# ADC_CURRENT_PUMP.net
KiCad netlist of a schematic drawn in Altium Designer
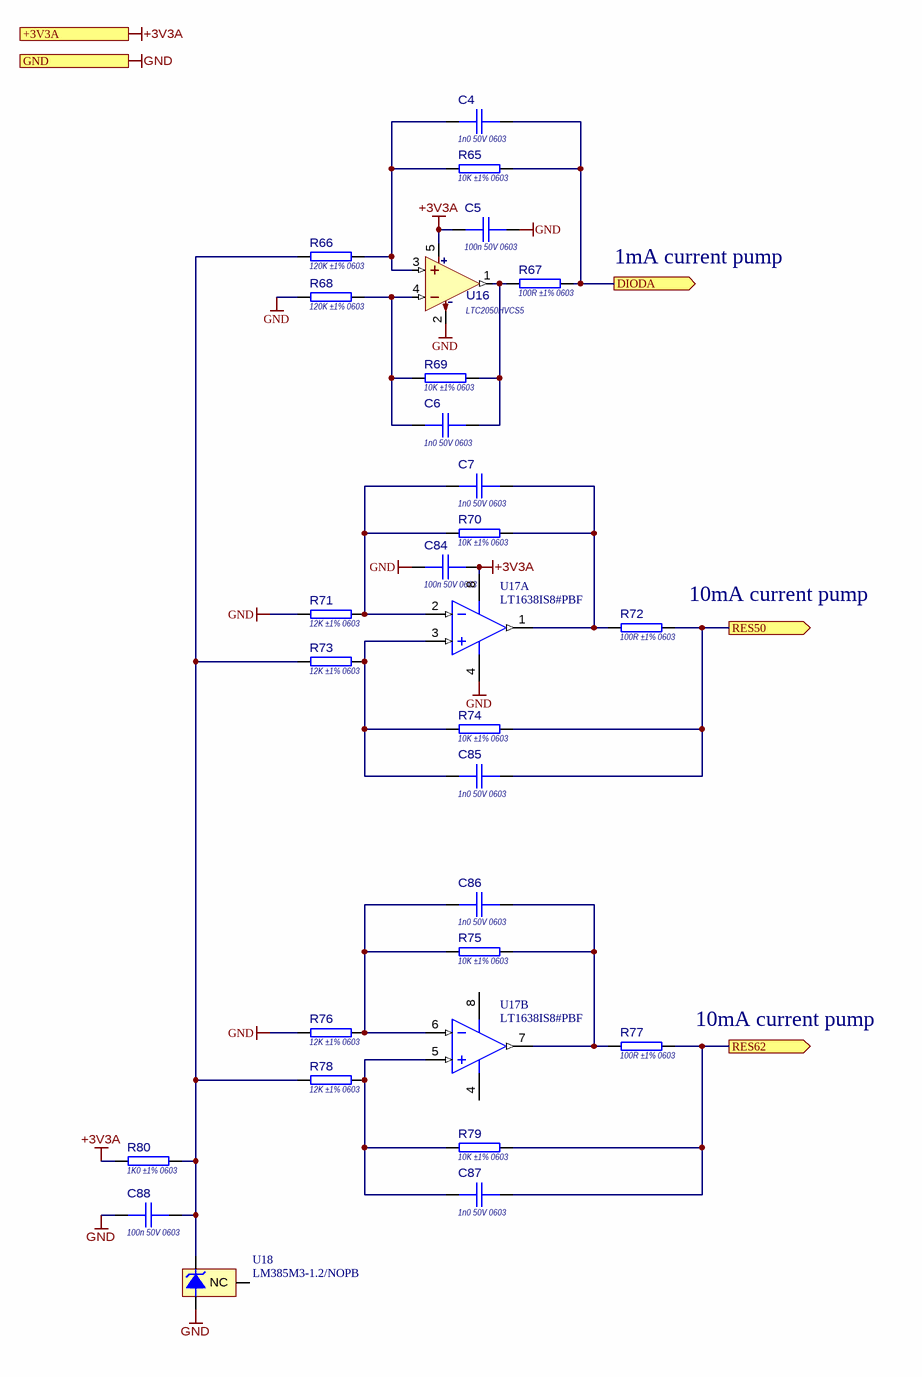
[diagram p0: ADC_CURRENT_PUMP.SchDoc]

(export (version "E")
  (design (tool "Eeschema 10.0.6"))
  (components
    (comp (ref "C4")
      (value "1n0 50V 0603")
      (footprint "CAPC1608X90N")
      (description "1n0 50V X7R ±10% 0603 (1608 metric)")
      (fields (field (name "PARTNUMBER") "GRM188R71H102KA01") (field (name "TOLERANCE") "±10%"))
      (libsource (lib "Omnisys Vault") (part "CAP-2PIN"))
    )
    (comp (ref "C5")
      (value "100n 50V 0603")
      (footprint "CAPC1608X90N")
      (description "100n 50V X7R ±10% 0603 (1608 metric)")
      (fields (field (name "PARTNUMBER") "GRM188R71H104KA93") (field (name "TOLERANCE") "±10%"))
      (libsource (lib "Omnisys Vault") (part "CAP-2PIN"))
    )
    (comp (ref "C6")
      (value "1n0 50V 0603")
      (footprint "CAPC1608X90N")
      (description "1n0 50V X7R ±10% 0603 (1608 metric)")
      (fields (field (name "PARTNUMBER") "GRM188R71H102KA01") (field (name "TOLERANCE") "±10%"))
      (libsource (lib "Omnisys Vault") (part "CAP-2PIN"))
    )
    (comp (ref "C7")
      (value "1n0 50V 0603")
      (footprint "CAPC1608X90N")
      (description "1n0 50V X7R ±10% 0603 (1608 metric)")
      (fields (field (name "PARTNUMBER") "GRM188R71H102KA01") (field (name "TOLERANCE") "±10%"))
      (libsource (lib "Omnisys Vault") (part "CAP-2PIN"))
    )
    (comp (ref "C84")
      (value "100n 50V 0603")
      (footprint "CAPC1608X90N")
      (description "100n 50V X7R ±10% 0603 (1608 metric)")
      (fields (field (name "PARTNUMBER") "GRM188R71H104KA93") (field (name "TOLERANCE") "±10%"))
      (libsource (lib "Omnisys Vault") (part "CAP-2PIN"))
    )
    (comp (ref "C85")
      (value "1n0 50V 0603")
      (footprint "CAPC1608X90N")
      (description "1n0 50V X7R ±10% 0603 (1608 metric)")
      (fields (field (name "PARTNUMBER") "GRM188R71H102KA01") (field (name "TOLERANCE") "±10%"))
      (libsource (lib "Omnisys Vault") (part "CAP-2PIN"))
    )
    (comp (ref "C86")
      (value "1n0 50V 0603")
      (footprint "CAPC1608X90N")
      (description "1n0 50V X7R ±10% 0603 (1608 metric)")
      (fields (field (name "PARTNUMBER") "GRM188R71H102KA01") (field (name "TOLERANCE") "±10%"))
      (libsource (lib "Omnisys Vault") (part "CAP-2PIN"))
    )
    (comp (ref "C87")
      (value "1n0 50V 0603")
      (footprint "CAPC1608X90N")
      (description "1n0 50V X7R ±10% 0603 (1608 metric)")
      (fields (field (name "PARTNUMBER") "GRM188R71H102KA01") (field (name "TOLERANCE") "±10%"))
      (libsource (lib "Omnisys Vault") (part "CAP-2PIN"))
    )
    (comp (ref "C88")
      (value "100n 50V 0603")
      (footprint "CAPC1608X90N")
      (description "100n 50V X7R ±10% 0603 (1608 metric)")
      (fields (field (name "PARTNUMBER") "GRM188R71H104KA93") (field (name "TOLERANCE") "±10%"))
      (libsource (lib "Omnisys Vault") (part "CAP-2PIN"))
    )
    (comp (ref "R65")
      (value "10K ±1% 0603")
      (footprint "RESC1608N")
      (description "10K ±1% ±100 ppm/˚C 0.10W 75V 0603 (1608 metric)")
      (fields (field (name "POWER") "100mW") (field (name "TOLERANCE") "1%"))
      (libsource (lib "Omnisys Vault") (part "RES-2PIN"))
    )
    (comp (ref "R66")
      (value "120K ±1% 0603")
      (footprint "RESC1608N")
      (description "120K ±1% ±100 ppm/˚C 0.10W 75V 0603 (1608 metric)")
      (fields (field (name "POWER") "100mW") (field (name "TOLERANCE") "1%"))
      (libsource (lib "Omnisys Vault") (part "RES-2PIN"))
    )
    (comp (ref "R67")
      (value "100R ±1% 0603")
      (footprint "RESC1608N")
      (description "100R ±1% ±100 ppm/˚C 0.10W 75V 0603 (1608 metric)")
      (fields (field (name "POWER") "100mW") (field (name "TOLERANCE") "1%"))
      (libsource (lib "Omnisys Vault") (part "RES-2PIN"))
    )
    (comp (ref "R68")
      (value "120K ±1% 0603")
      (footprint "RESC1608N")
      (description "120K ±1% ±100 ppm/˚C 0.10W 75V 0603 (1608 metric)")
      (fields (field (name "POWER") "100mW") (field (name "TOLERANCE") "1%"))
      (libsource (lib "Omnisys Vault") (part "RES-2PIN"))
    )
    (comp (ref "R69")
      (value "10K ±1% 0603")
      (footprint "RESC1608N")
      (description "10K ±1% ±100 ppm/˚C 0.10W 75V 0603 (1608 metric)")
      (fields (field (name "POWER") "100mW") (field (name "TOLERANCE") "1%"))
      (libsource (lib "Omnisys Vault") (part "RES-2PIN"))
    )
    (comp (ref "R70")
      (value "10K ±1% 0603")
      (footprint "RESC1608N")
      (description "10K ±1% ±100 ppm/˚C 0.10W 75V 0603 (1608 metric)")
      (fields (field (name "POWER") "100mW") (field (name "TOLERANCE") "1%"))
      (libsource (lib "Omnisys Vault") (part "RES-2PIN"))
    )
    (comp (ref "R71")
      (value "12K ±1% 0603")
      (footprint "RESC1608N")
      (description "12K ±1% ±100 ppm/˚C 0.10W 75V 0603 (1608 metric)")
      (fields (field (name "POWER") "100mW") (field (name "TOLERANCE") "1%"))
      (libsource (lib "Omnisys Vault") (part "RES-2PIN"))
    )
    (comp (ref "R72")
      (value "100R ±1% 0603")
      (footprint "RESC1608N")
      (description "100R ±1% ±100 ppm/˚C 0.10W 75V 0603 (1608 metric)")
      (fields (field (name "POWER") "100mW") (field (name "TOLERANCE") "1%"))
      (libsource (lib "Omnisys Vault") (part "RES-2PIN"))
    )
    (comp (ref "R73")
      (value "12K ±1% 0603")
      (footprint "RESC1608N")
      (description "12K ±1% ±100 ppm/˚C 0.10W 75V 0603 (1608 metric)")
      (fields (field (name "POWER") "100mW") (field (name "TOLERANCE") "1%"))
      (libsource (lib "Omnisys Vault") (part "RES-2PIN"))
    )
    (comp (ref "R74")
      (value "10K ±1% 0603")
      (footprint "RESC1608N")
      (description "10K ±1% ±100 ppm/˚C 0.10W 75V 0603 (1608 metric)")
      (fields (field (name "POWER") "100mW") (field (name "TOLERANCE") "1%"))
      (libsource (lib "Omnisys Vault") (part "RES-2PIN"))
    )
    (comp (ref "R75")
      (value "10K ±1% 0603")
      (footprint "RESC1608N")
      (description "10K ±1% ±100 ppm/˚C 0.10W 75V 0603 (1608 metric)")
      (fields (field (name "POWER") "100mW") (field (name "TOLERANCE") "1%"))
      (libsource (lib "Omnisys Vault") (part "RES-2PIN"))
    )
    (comp (ref "R76")
      (value "12K ±1% 0603")
      (footprint "RESC1608N")
      (description "12K ±1% ±100 ppm/˚C 0.10W 75V 0603 (1608 metric)")
      (fields (field (name "POWER") "100mW") (field (name "TOLERANCE") "1%"))
      (libsource (lib "Omnisys Vault") (part "RES-2PIN"))
    )
    (comp (ref "R77")
      (value "100R ±1% 0603")
      (footprint "RESC1608N")
      (description "100R ±1% ±100 ppm/˚C 0.10W 75V 0603 (1608 metric)")
      (fields (field (name "POWER") "100mW") (field (name "TOLERANCE") "1%"))
      (libsource (lib "Omnisys Vault") (part "RES-2PIN"))
    )
    (comp (ref "R78")
      (value "12K ±1% 0603")
      (footprint "RESC1608N")
      (description "12K ±1% ±100 ppm/˚C 0.10W 75V 0603 (1608 metric)")
      (fields (field (name "POWER") "100mW") (field (name "TOLERANCE") "1%"))
      (libsource (lib "Omnisys Vault") (part "RES-2PIN"))
    )
    (comp (ref "R79")
      (value "10K ±1% 0603")
      (footprint "RESC1608N")
      (description "10K ±1% ±100 ppm/˚C 0.10W 75V 0603 (1608 metric)")
      (fields (field (name "POWER") "100mW") (field (name "TOLERANCE") "1%"))
      (libsource (lib "Omnisys Vault") (part "RES-2PIN"))
    )
    (comp (ref "R80")
      (value "1K0 ±1% 0603")
      (footprint "RESC1608N")
      (description "1K0 ±1% ±100 ppm/˚C 0.10W 75V 0603 (1608 metric)")
      (fields (field (name "TOLERANCE") "1%") (field (name "POWER") "100mW"))
      (libsource (lib "Omnisys Vault") (part "RES-2PIN"))
    )
    (comp (ref "U16")
      (value "LTC2050HVCS5")
      (footprint "SOT95P280X100-5N")
      (description "Zero-Drift Operational Amplifiers in SOT-23")
      (libsource (lib "Omnisys Vault") (part "OPAMP-SOT23-5"))
    )
    (comp (ref "U17")
      (value "LT1638IS8#PBF")
      (footprint "LT-S8-8_N")
      (fields
        (field (name "LINEAR TECHNOLOGY PART NUMBER") "LT1638")
        (field (name "MANUFACTURER") "Linear Technology")
      )
      (libsource (lib "Altium Content Vault") (part "LT-LT1638-S8-8"))
    )
    (comp (ref "U18")
      (value "LM385M3-1.2/NOPB")
      (footprint "DBZ0003A_L")
      (description "Micropower Voltage Reference Diode, 3-pin SOT-23, Pb-Free")
      (fields (field (name "MANUFACTURER") "Texas Instruments"))
      (libsource (lib "Altium Content Vault") (part "PM-REF-LM113-SOT3"))
    )
  )
  (nets
    (net (code "1") (name "+3V3A") (class "Default")
      (node (ref "C5") (pin "2") (pinfunction "2_2") (pintype "passive"))
      (node (ref "C84") (pin "2") (pinfunction "2_2") (pintype "passive"))
      (node (ref "R80") (pin "2") (pinfunction "2_2") (pintype "passive"))
      (node (ref "U16") (pin "5") (pinfunction "+V_5") (pintype "power_in"))
      (node (ref "U17") (pin "8") (pinfunction "V+_8") (pintype "power_in"))
    )
    (net (code "2") (name "/DIODA") (class "Default")
      (node (ref "C4") (pin "1") (pinfunction "1_1") (pintype "passive"))
      (node (ref "R65") (pin "2") (pinfunction "2_2") (pintype "passive"))
      (node (ref "R67") (pin "1") (pinfunction "1_1") (pintype "passive"))
    )
    (net (code "3") (name "/RES50") (class "Default")
      (node (ref "C85") (pin "1") (pinfunction "1_1") (pintype "passive"))
      (node (ref "R72") (pin "1") (pinfunction "1_1") (pintype "passive"))
      (node (ref "R74") (pin "2") (pinfunction "2_2") (pintype "passive"))
    )
    (net (code "4") (name "/RES62") (class "Default")
      (node (ref "C87") (pin "1") (pinfunction "1_1") (pintype "passive"))
      (node (ref "R77") (pin "1") (pinfunction "1_1") (pintype "passive"))
      (node (ref "R79") (pin "1") (pinfunction "1_1") (pintype "passive"))
    )
    (net (code "5") (name "GND") (class "Default")
      (node (ref "C5") (pin "1") (pinfunction "1_1") (pintype "passive"))
      (node (ref "C84") (pin "1") (pinfunction "1_1") (pintype "passive"))
      (node (ref "C88") (pin "1") (pinfunction "1_1") (pintype "passive"))
      (node (ref "R68") (pin "1") (pinfunction "1_1") (pintype "passive"))
      (node (ref "R71") (pin "1") (pinfunction "1_1") (pintype "passive"))
      (node (ref "R76") (pin "1") (pinfunction "1_1") (pintype "passive"))
      (node (ref "U16") (pin "2") (pinfunction "-V_2") (pintype "power_in"))
      (node (ref "U17") (pin "4") (pinfunction "V-_4") (pintype "power_in"))
      (node (ref "U18") (pin "2") (pinfunction "-V_2") (pintype "passive"))
    )
    (net (code "6") (name "Net-(U16-+IN)") (class "Default")
      (node (ref "C4") (pin "2") (pinfunction "2_2") (pintype "passive"))
      (node (ref "R65") (pin "1") (pinfunction "1_1") (pintype "passive"))
      (node (ref "R66") (pin "2") (pinfunction "2_2") (pintype "passive"))
      (node (ref "U16") (pin "3") (pinfunction "+IN_3") (pintype "input"))
    )
    (net (code "7") (name "Net-(U16--IN)") (class "Default")
      (node (ref "C6") (pin "2") (pinfunction "2_2") (pintype "passive"))
      (node (ref "R68") (pin "2") (pinfunction "2_2") (pintype "passive"))
      (node (ref "R69") (pin "1") (pinfunction "1_1") (pintype "passive"))
      (node (ref "U16") (pin "4") (pinfunction "-IN_4") (pintype "input"))
    )
    (net (code "8") (name "Net-(U16-OUT)") (class "Default")
      (node (ref "C6") (pin "1") (pinfunction "1_1") (pintype "passive"))
      (node (ref "R67") (pin "2") (pinfunction "2_2") (pintype "passive"))
      (node (ref "R69") (pin "2") (pinfunction "2_2") (pintype "passive"))
      (node (ref "U16") (pin "1") (pinfunction "OUT_1") (pintype "output"))
    )
    (net (code "9") (name "Net-(U17A-+IN_A)") (class "Default")
      (node (ref "C85") (pin "2") (pinfunction "2_2") (pintype "passive"))
      (node (ref "R73") (pin "2") (pinfunction "2_2") (pintype "passive"))
      (node (ref "R74") (pin "1") (pinfunction "1_1") (pintype "passive"))
      (node (ref "U17") (pin "3") (pinfunction "+IN_A_3") (pintype "input"))
    )
    (net (code "10") (name "Net-(U17A--IN_A)") (class "Default")
      (node (ref "C7") (pin "2") (pinfunction "2_2") (pintype "passive"))
      (node (ref "R70") (pin "2") (pinfunction "2_2") (pintype "passive"))
      (node (ref "R71") (pin "2") (pinfunction "2_2") (pintype "passive"))
      (node (ref "U17") (pin "2") (pinfunction "-IN_A_2") (pintype "input"))
    )
    (net (code "11") (name "Net-(U17A-OUT_A)") (class "Default")
      (node (ref "C7") (pin "1") (pinfunction "1_1") (pintype "passive"))
      (node (ref "R70") (pin "1") (pinfunction "1_1") (pintype "passive"))
      (node (ref "R72") (pin "2") (pinfunction "2_2") (pintype "passive"))
      (node (ref "U17") (pin "1") (pinfunction "OUT_A_1") (pintype "output"))
    )
    (net (code "12") (name "Net-(U17B-+IN_B)") (class "Default")
      (node (ref "C87") (pin "2") (pinfunction "2_2") (pintype "passive"))
      (node (ref "R78") (pin "2") (pinfunction "2_2") (pintype "passive"))
      (node (ref "R79") (pin "2") (pinfunction "2_2") (pintype "passive"))
      (node (ref "U17") (pin "5") (pinfunction "+IN_B_5") (pintype "input"))
    )
    (net (code "13") (name "Net-(U17B--IN_B)") (class "Default")
      (node (ref "C86") (pin "2") (pinfunction "2_2") (pintype "passive"))
      (node (ref "R75") (pin "2") (pinfunction "2_2") (pintype "passive"))
      (node (ref "R76") (pin "2") (pinfunction "2_2") (pintype "passive"))
      (node (ref "U17") (pin "6") (pinfunction "-IN_B_6") (pintype "input"))
    )
    (net (code "14") (name "Net-(U17B-OUT_B)") (class "Default")
      (node (ref "C86") (pin "1") (pinfunction "1_1") (pintype "passive"))
      (node (ref "R75") (pin "1") (pinfunction "1_1") (pintype "passive"))
      (node (ref "R77") (pin "2") (pinfunction "2_2") (pintype "passive"))
      (node (ref "U17") (pin "7") (pinfunction "OUT_B_7") (pintype "output"))
    )
    (net (code "15") (name "Net-(U18-+V)") (class "Default")
      (node (ref "C88") (pin "2") (pinfunction "2_2") (pintype "passive"))
      (node (ref "R66") (pin "1") (pinfunction "1_1") (pintype "passive"))
      (node (ref "R73") (pin "1") (pinfunction "1_1") (pintype "passive"))
      (node (ref "R78") (pin "1") (pinfunction "1_1") (pintype "passive"))
      (node (ref "R80") (pin "1") (pinfunction "1_1") (pintype "passive"))
      (node (ref "U18") (pin "1") (pinfunction "+V_1") (pintype "passive"))
    )
    (net (code "16") (name "unconnected-(U17B-V+-Pad8)") (class "Default")
      (node (ref "U17") (pin "8") (pinfunction "V+_8") (pintype "power_in"))
    )
    (net (code "17") (name "unconnected-(U17B-V--Pad4)") (class "Default")
      (node (ref "U17") (pin "4") (pinfunction "V-_4") (pintype "power_in"))
    )
    (net (code "18") (name "unconnected-(U18-NC-Pad3)") (class "Default")
      (node (ref "U18") (pin "3") (pinfunction "NC_3") (pintype "passive"))
    )
  )
)
